# USBCONN_C_16_and_A.net
KiCad netlist of a schematic drawn in Altium Designer
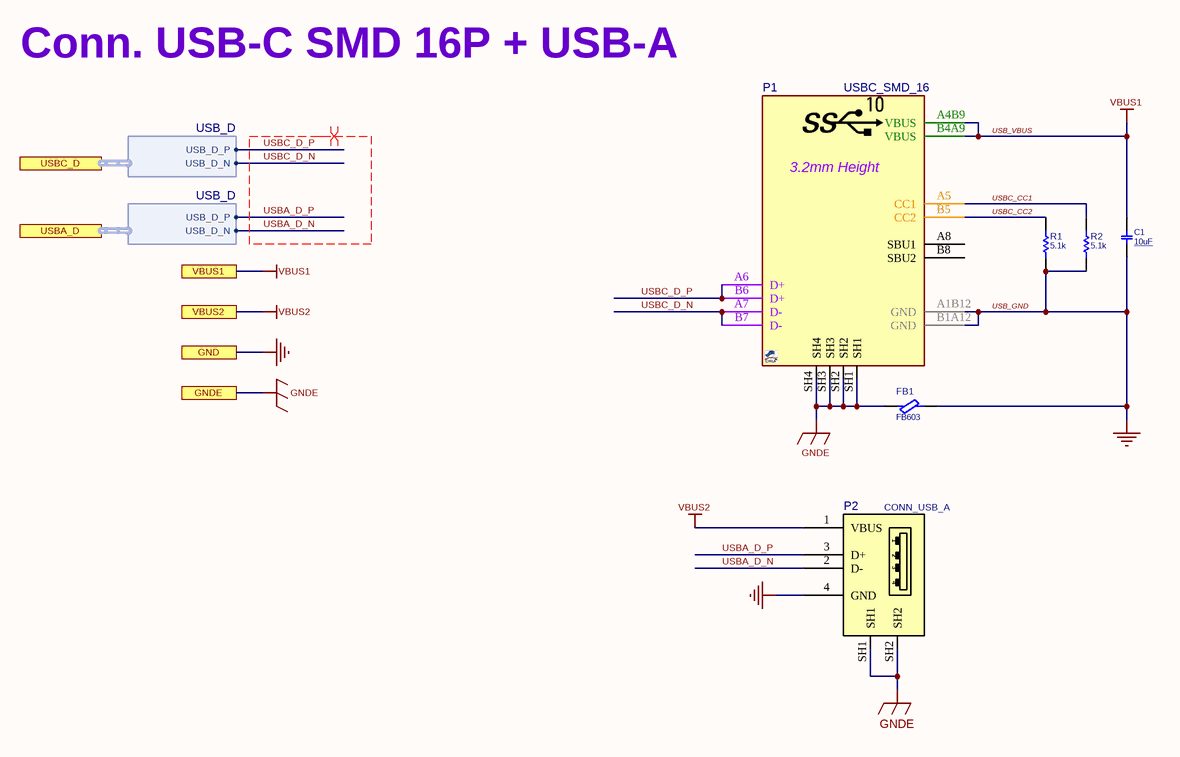
[diagram p0: USBCONN_C_16_and_A.SchDoc]

(export (version "E")
  (design (tool "Eeschema 10.0.6"))
  (components
    (comp (ref "C1")
      (value "10uF")
      (footprint "C0402")
      (description "CAP, MLCC")
      (fields (field (name "MANF") "Murata"))
      (libsource (lib "mlcc_smd_passive") (part "CAP_SMD_MLCC"))
    )
    (comp (ref "FB1")
      (value "FB603")
      (footprint "L0603")
      (description "FERRITE_Bead, 0603, 1.3A, 150mOhm, 600@100MHz")
      (fields (field (name "MANF") "MURATA") (field (name "MANF_P#") "BLM18KG601SN1D"))
      (libsource (lib "emi_filter") (part "FBEAD_SMD_BLM18KG601"))
    )
    (comp (ref "P1")
      (value "USBC_SMD_16")
      (footprint "USBC_SMD_16_2171790001")
      (description "CONN, USB, Type C, USB 2.0, Right-Angle, SMD")
      (fields (field (name "MANF") "MOLEX") (field (name "MANF_P#") "2171790001"))
      (libsource (lib "USBC") (part "CONN_USBC_SMD_16_2171790001"))
    )
    (comp (ref "P2")
      (value "CONN_USB_A")
      (footprint "USB_A_REC_RA_THD_S")
      (description "CONN, USB, A, RECEPTACLE, R/A, THD")
      (fields (field (name "MANF_P#") "USBC125"))
      (libsource (lib "conn_usb") (part "CONN_USB_A_REC_RA_THD_SHORT"))
    )
    (comp (ref "R1")
      (value "5.1k")
      (footprint "R0402")
      (description "RESISTOR, SMD")
      (libsource (lib "res_smd_passive") (part "RES_SMD"))
    )
    (comp (ref "R2")
      (value "5.1k")
      (footprint "R0402")
      (description "RESISTOR, SMD")
      (libsource (lib "res_smd_passive") (part "RES_SMD"))
    )
  )
  (nets
    (net (code "2") (name "/USBA_D_N") (class "Default")
      (node (ref "P2") (pin "2") (pinfunction "D-_2") (pintype "passive"))
    )
    (net (code "3") (name "/USBA_D_P") (class "Default")
      (node (ref "P2") (pin "3") (pinfunction "D+_3") (pintype "passive"))
    )
    (net (code "4") (name "/USBC_CC1") (class "Default")
      (node (ref "P1") (pin "A5") (pinfunction "CC1_A5") (pintype "passive"))
      (node (ref "R2") (pin "2") (pinfunction "2_2") (pintype "passive"))
    )
    (net (code "5") (name "/USBC_CC2") (class "Default")
      (node (ref "P1") (pin "B5") (pinfunction "CC2_B5") (pintype "passive"))
      (node (ref "R1") (pin "2") (pinfunction "2_2") (pintype "passive"))
    )
    (net (code "6") (name "/USBC_D_N") (class "Default")
      (node (ref "P1") (pin "A7") (pinfunction "D-_A7") (pintype "passive"))
      (node (ref "P1") (pin "B7") (pinfunction "D-_B7") (pintype "passive"))
    )
    (net (code "7") (name "/USBC_D_P") (class "Default")
      (node (ref "P1") (pin "A6") (pinfunction "D+_A6") (pintype "passive"))
      (node (ref "P1") (pin "B6") (pinfunction "D+_B6") (pintype "passive"))
    )
    (net (code "9") (name "GND") (class "Default")
      (node (ref "C1") (pin "2") (pinfunction "2_2") (pintype "passive"))
      (node (ref "FB1") (pin "2") (pinfunction "2_2") (pintype "passive"))
      (node (ref "P1") (pin "A1B12") (pinfunction "GND_A1B12") (pintype "passive"))
      (node (ref "P1") (pin "B1A12") (pinfunction "GND_B1A12") (pintype "passive"))
      (node (ref "P2") (pin "4") (pinfunction "GND_4") (pintype "passive"))
      (node (ref "R1") (pin "1") (pinfunction "1_1") (pintype "passive"))
      (node (ref "R2") (pin "1") (pinfunction "1_1") (pintype "passive"))
    )
    (net (code "10") (name "GNDE") (class "Default")
      (node (ref "FB1") (pin "1") (pinfunction "1_1") (pintype "passive"))
      (node (ref "P1") (pin "SH1") (pinfunction "SH1_SH1") (pintype "passive"))
      (node (ref "P1") (pin "SH2") (pinfunction "SH2_SH2") (pintype "passive"))
      (node (ref "P1") (pin "SH3") (pinfunction "SH3_SH3") (pintype "passive"))
      (node (ref "P1") (pin "SH4") (pinfunction "SH4_SH4") (pintype "passive"))
      (node (ref "P2") (pin "SH1") (pinfunction "SH1_SH1") (pintype "passive"))
      (node (ref "P2") (pin "SH2") (pinfunction "SH2_SH2") (pintype "passive"))
    )
    (net (code "11") (name "VBUS1") (class "Default")
      (node (ref "C1") (pin "1") (pinfunction "1_1") (pintype "passive"))
      (node (ref "P1") (pin "A4B9") (pinfunction "VBUS_A4B9") (pintype "passive"))
      (node (ref "P1") (pin "B4A9") (pinfunction "VBUS_B4A9") (pintype "passive"))
    )
    (net (code "12") (name "VBUS2") (class "Default")
      (node (ref "P2") (pin "1") (pinfunction "VBUS_1") (pintype "passive"))
    )
    (net (code "13") (name "unconnected-(P1-SBU1-PadA8)") (class "Default")
      (node (ref "P1") (pin "A8") (pinfunction "SBU1_A8") (pintype "passive"))
    )
    (net (code "14") (name "unconnected-(P1-SBU2-PadB8)") (class "Default")
      (node (ref "P1") (pin "B8") (pinfunction "SBU2_B8") (pintype "passive"))
    )
  )
)
